# easyeda.net
KiCad netlist of a schematic drawn in EasyEDA
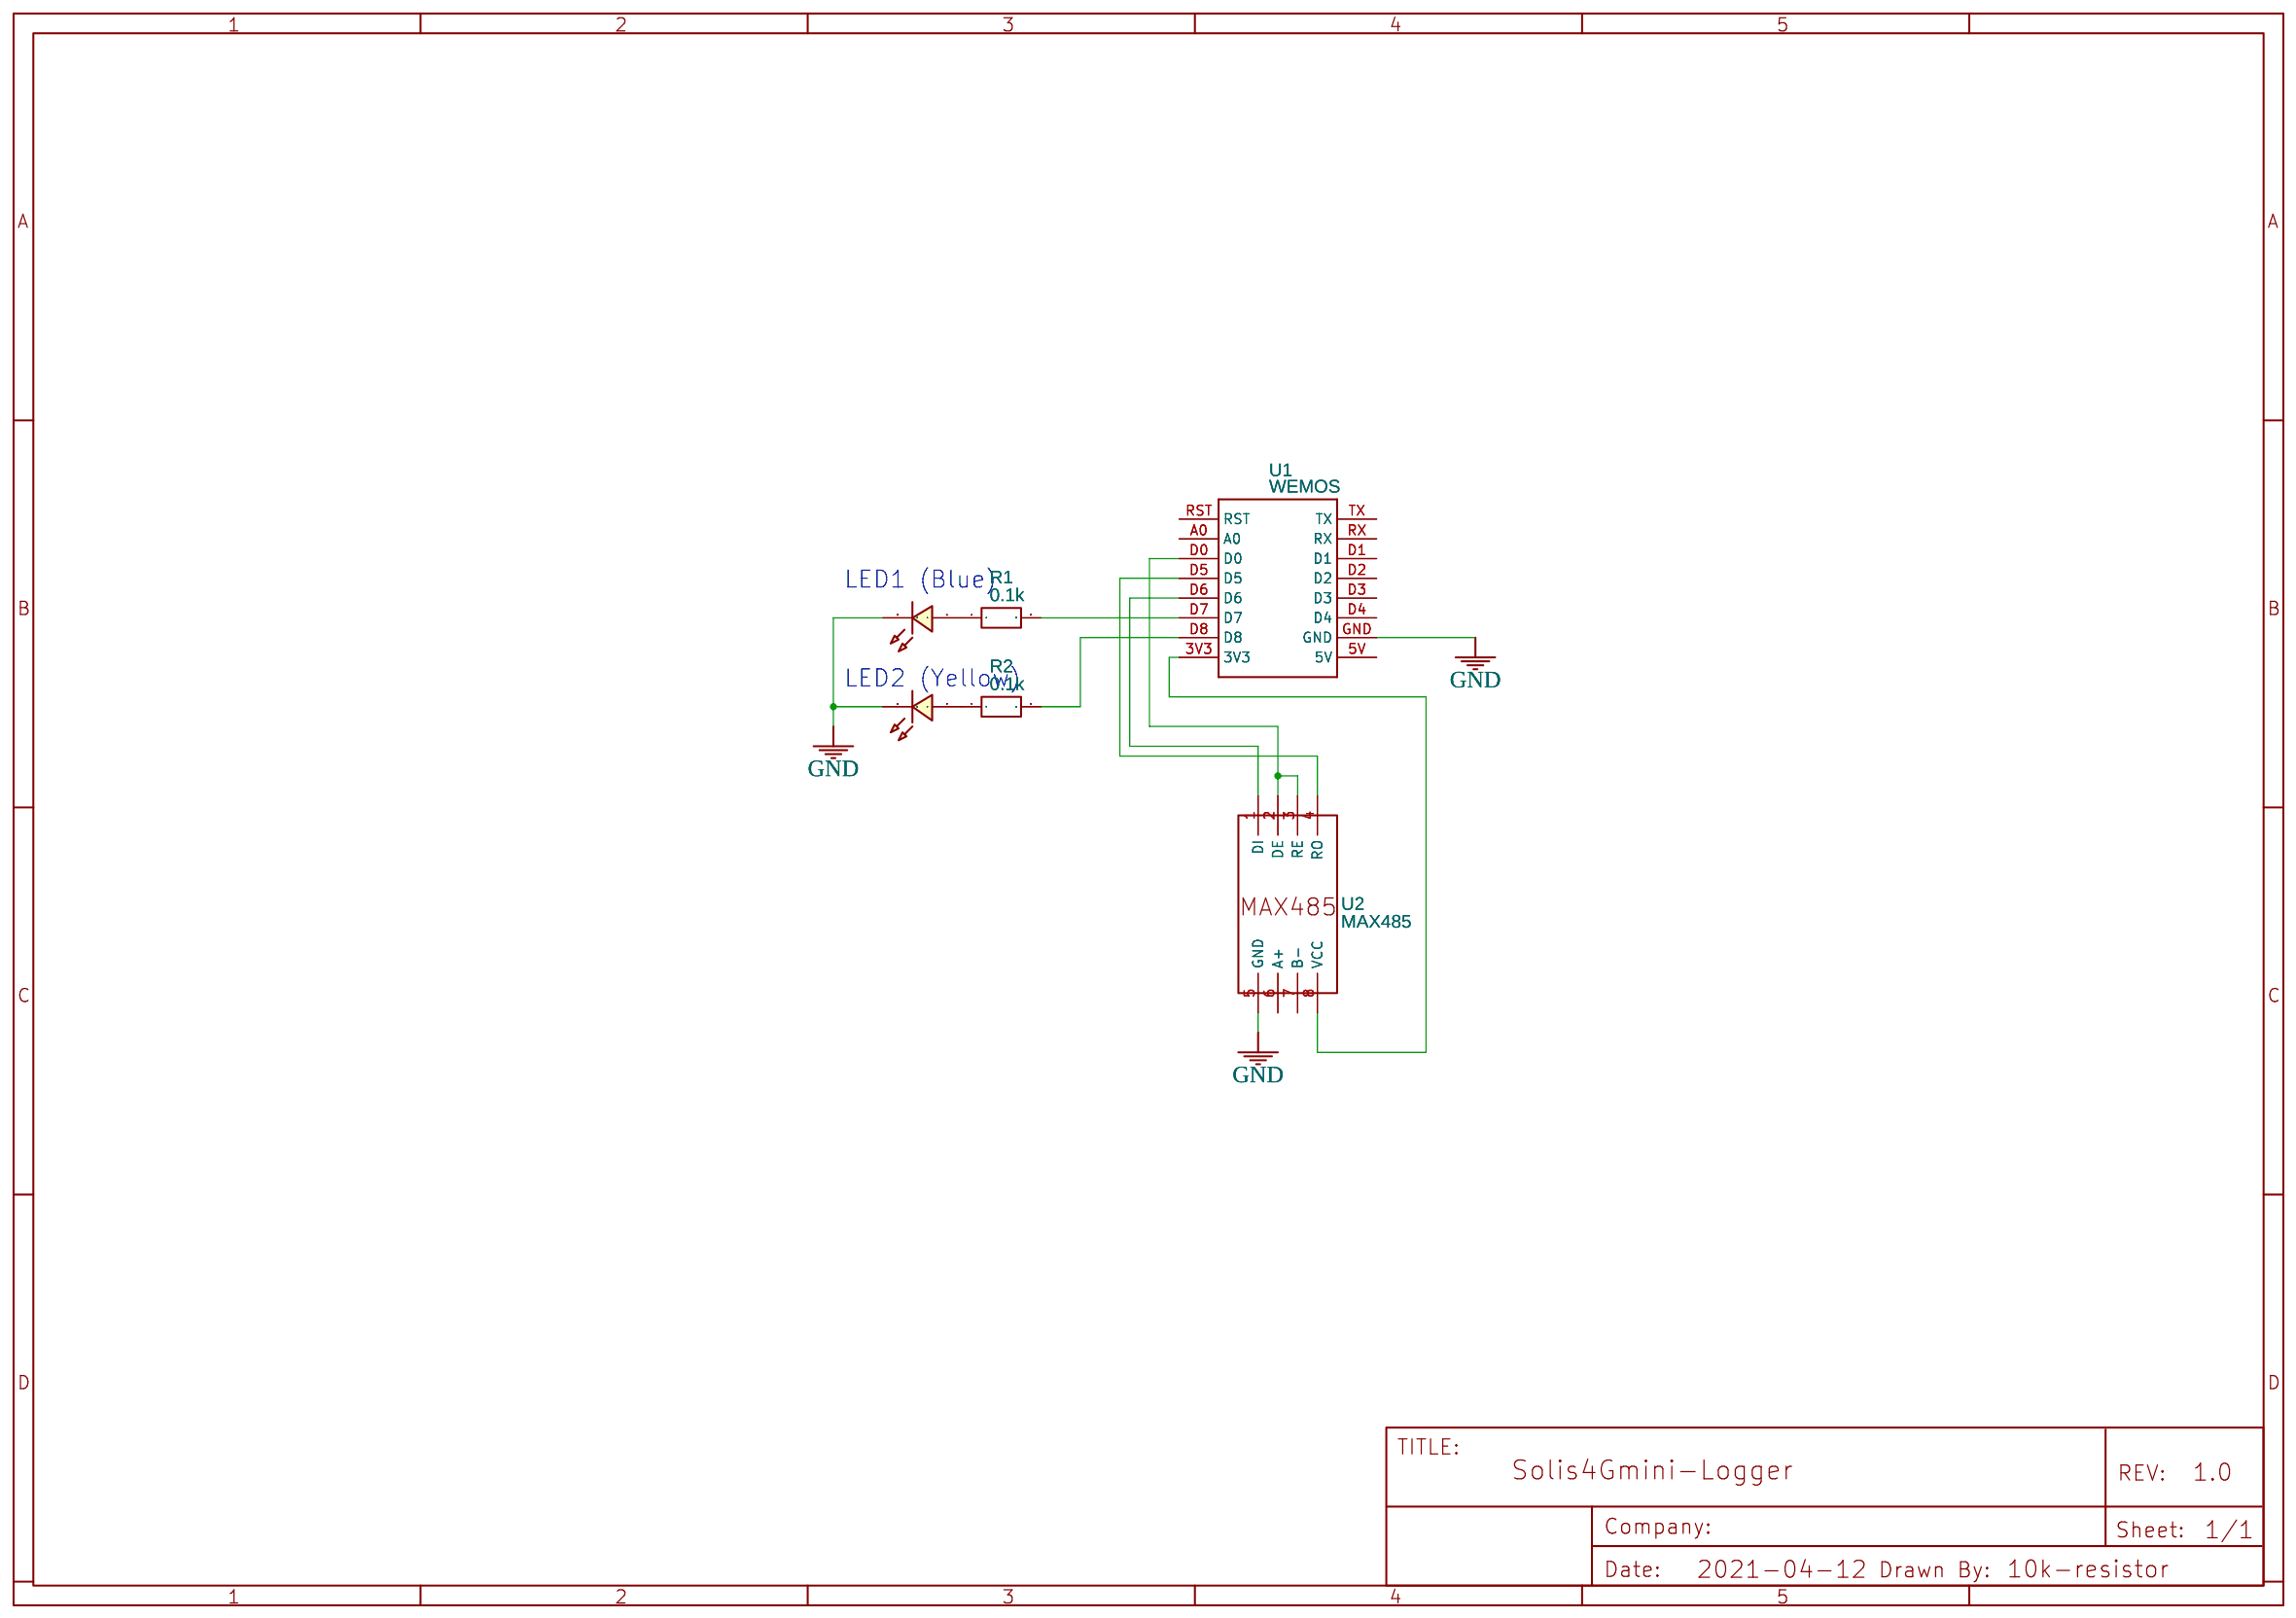
[diagram p0: schematic sheet]

(export (version "E")
  (design (tool "Eeschema 10.0.6"))
  (components
    (comp (ref "LED1")
      (value "LED-0603_R")
      (fields
        (field (name "BOM_Manufacturer Part") "19-217/R6C-AL1M2VY/3T")
        (field (name "BOM_Supplier Part") "C72044")
      )
      (libsource (lib "") (part "LED-0603_R"))
    )
    (comp (ref "LED2")
      (value "LED-0603_R")
      (fields
        (field (name "BOM_Manufacturer Part") "19-217/R6C-AL1M2VY/3T")
        (field (name "BOM_Supplier Part") "C72044")
      )
      (libsource (lib "") (part "LED-0603_R"))
    )
    (comp (ref "R1") (value "0.1k") (libsource (lib "") (part "R_0603_EU")))
    (comp (ref "R2") (value "0.1k") (libsource (lib "") (part "R_0603_EU")))
    (comp (ref "U1") (value "WEMOS") (libsource (lib "") (part "WEMOS")))
    (comp (ref "U2") (value "MAX485") (libsource (lib "") (part "MAX485")))
  )
  (nets
    (net (code "1") (name "GND") (class "Default")
      (node (ref "LED1") (pin "2") (pinfunction "2_2") (pintype "unspecified"))
      (node (ref "LED2") (pin "2") (pinfunction "2_2") (pintype "unspecified"))
      (node (ref "U1") (pin "GND") (pinfunction "GND_GND") (pintype "unspecified"))
      (node (ref "U2") (pin "5") (pinfunction "GND_5") (pintype "unspecified"))
    )
    (net (code "2") (name "Net-(LED1-Pad1)") (class "Default")
      (node (ref "LED1") (pin "1") (pinfunction "1_1") (pintype "unspecified"))
      (node (ref "R1") (pin "1") (pinfunction "1_1") (pintype "unspecified"))
    )
    (net (code "3") (name "Net-(LED2-Pad1)") (class "Default")
      (node (ref "LED2") (pin "1") (pinfunction "1_1") (pintype "unspecified"))
      (node (ref "R2") (pin "1") (pinfunction "1_1") (pintype "unspecified"))
    )
    (net (code "4") (name "Net-(R1-Pad2)") (class "Default")
      (node (ref "R1") (pin "2") (pinfunction "2_2") (pintype "unspecified"))
      (node (ref "U1") (pin "D7") (pinfunction "D7_D7") (pintype "unspecified"))
    )
    (net (code "5") (name "Net-(R2-Pad2)") (class "Default")
      (node (ref "R2") (pin "2") (pinfunction "2_2") (pintype "unspecified"))
      (node (ref "U1") (pin "D8") (pinfunction "D8_D8") (pintype "unspecified"))
    )
    (net (code "6") (name "Net-(U2-DE)") (class "Default")
      (node (ref "U1") (pin "D0") (pinfunction "D0_D0") (pintype "unspecified"))
      (node (ref "U2") (pin "2") (pinfunction "DE_2") (pintype "unspecified"))
      (node (ref "U2") (pin "3") (pinfunction "RE_3") (pintype "unspecified"))
    )
    (net (code "7") (name "Net-(U2-DI)") (class "Default")
      (node (ref "U1") (pin "D6") (pinfunction "D6_D6") (pintype "unspecified"))
      (node (ref "U2") (pin "1") (pinfunction "DI_1") (pintype "unspecified"))
    )
    (net (code "8") (name "Net-(U2-RO)") (class "Default")
      (node (ref "U1") (pin "D5") (pinfunction "D5_D5") (pintype "unspecified"))
      (node (ref "U2") (pin "4") (pinfunction "RO_4") (pintype "unspecified"))
    )
    (net (code "9") (name "Net-(U2-VCC)") (class "Default")
      (node (ref "U1") (pin "3V3") (pinfunction "3V3_3V3") (pintype "unspecified"))
      (node (ref "U2") (pin "8") (pinfunction "VCC_8") (pintype "unspecified"))
    )
    (net (code "10") (name "unconnected-(U1-Pad5V)") (class "Default")
      (node (ref "U1") (pin "5V") (pinfunction "5V_5V") (pintype "unspecified"))
    )
    (net (code "11") (name "unconnected-(U1-PadA0)") (class "Default")
      (node (ref "U1") (pin "A0") (pinfunction "A0_A0") (pintype "unspecified"))
    )
    (net (code "12") (name "unconnected-(U1-PadD1)") (class "Default")
      (node (ref "U1") (pin "D1") (pinfunction "D1_D1") (pintype "unspecified"))
    )
    (net (code "13") (name "unconnected-(U1-PadD2)") (class "Default")
      (node (ref "U1") (pin "D2") (pinfunction "D2_D2") (pintype "unspecified"))
    )
    (net (code "14") (name "unconnected-(U1-PadD3)") (class "Default")
      (node (ref "U1") (pin "D3") (pinfunction "D3_D3") (pintype "unspecified"))
    )
    (net (code "15") (name "unconnected-(U1-PadD4)") (class "Default")
      (node (ref "U1") (pin "D4") (pinfunction "D4_D4") (pintype "unspecified"))
    )
    (net (code "16") (name "unconnected-(U1-PadRST)") (class "Default")
      (node (ref "U1") (pin "RST") (pinfunction "RST_RST") (pintype "unspecified"))
    )
    (net (code "17") (name "unconnected-(U1-PadRX)") (class "Default")
      (node (ref "U1") (pin "RX") (pinfunction "RX_RX") (pintype "unspecified"))
    )
    (net (code "18") (name "unconnected-(U1-PadTX)") (class "Default")
      (node (ref "U1") (pin "TX") (pinfunction "TX_TX") (pintype "unspecified"))
    )
    (net (code "19") (name "unconnected-(U2-A+-Pad6)") (class "Default")
      (node (ref "U2") (pin "6") (pinfunction "A+_6") (pintype "unspecified"))
    )
    (net (code "20") (name "unconnected-(U2-B--Pad7)") (class "Default")
      (node (ref "U2") (pin "7") (pinfunction "B-_7") (pintype "unspecified"))
    )
  )
)
